# Sensor_Sound.net
KiCad netlist of a schematic drawn in EAGLE
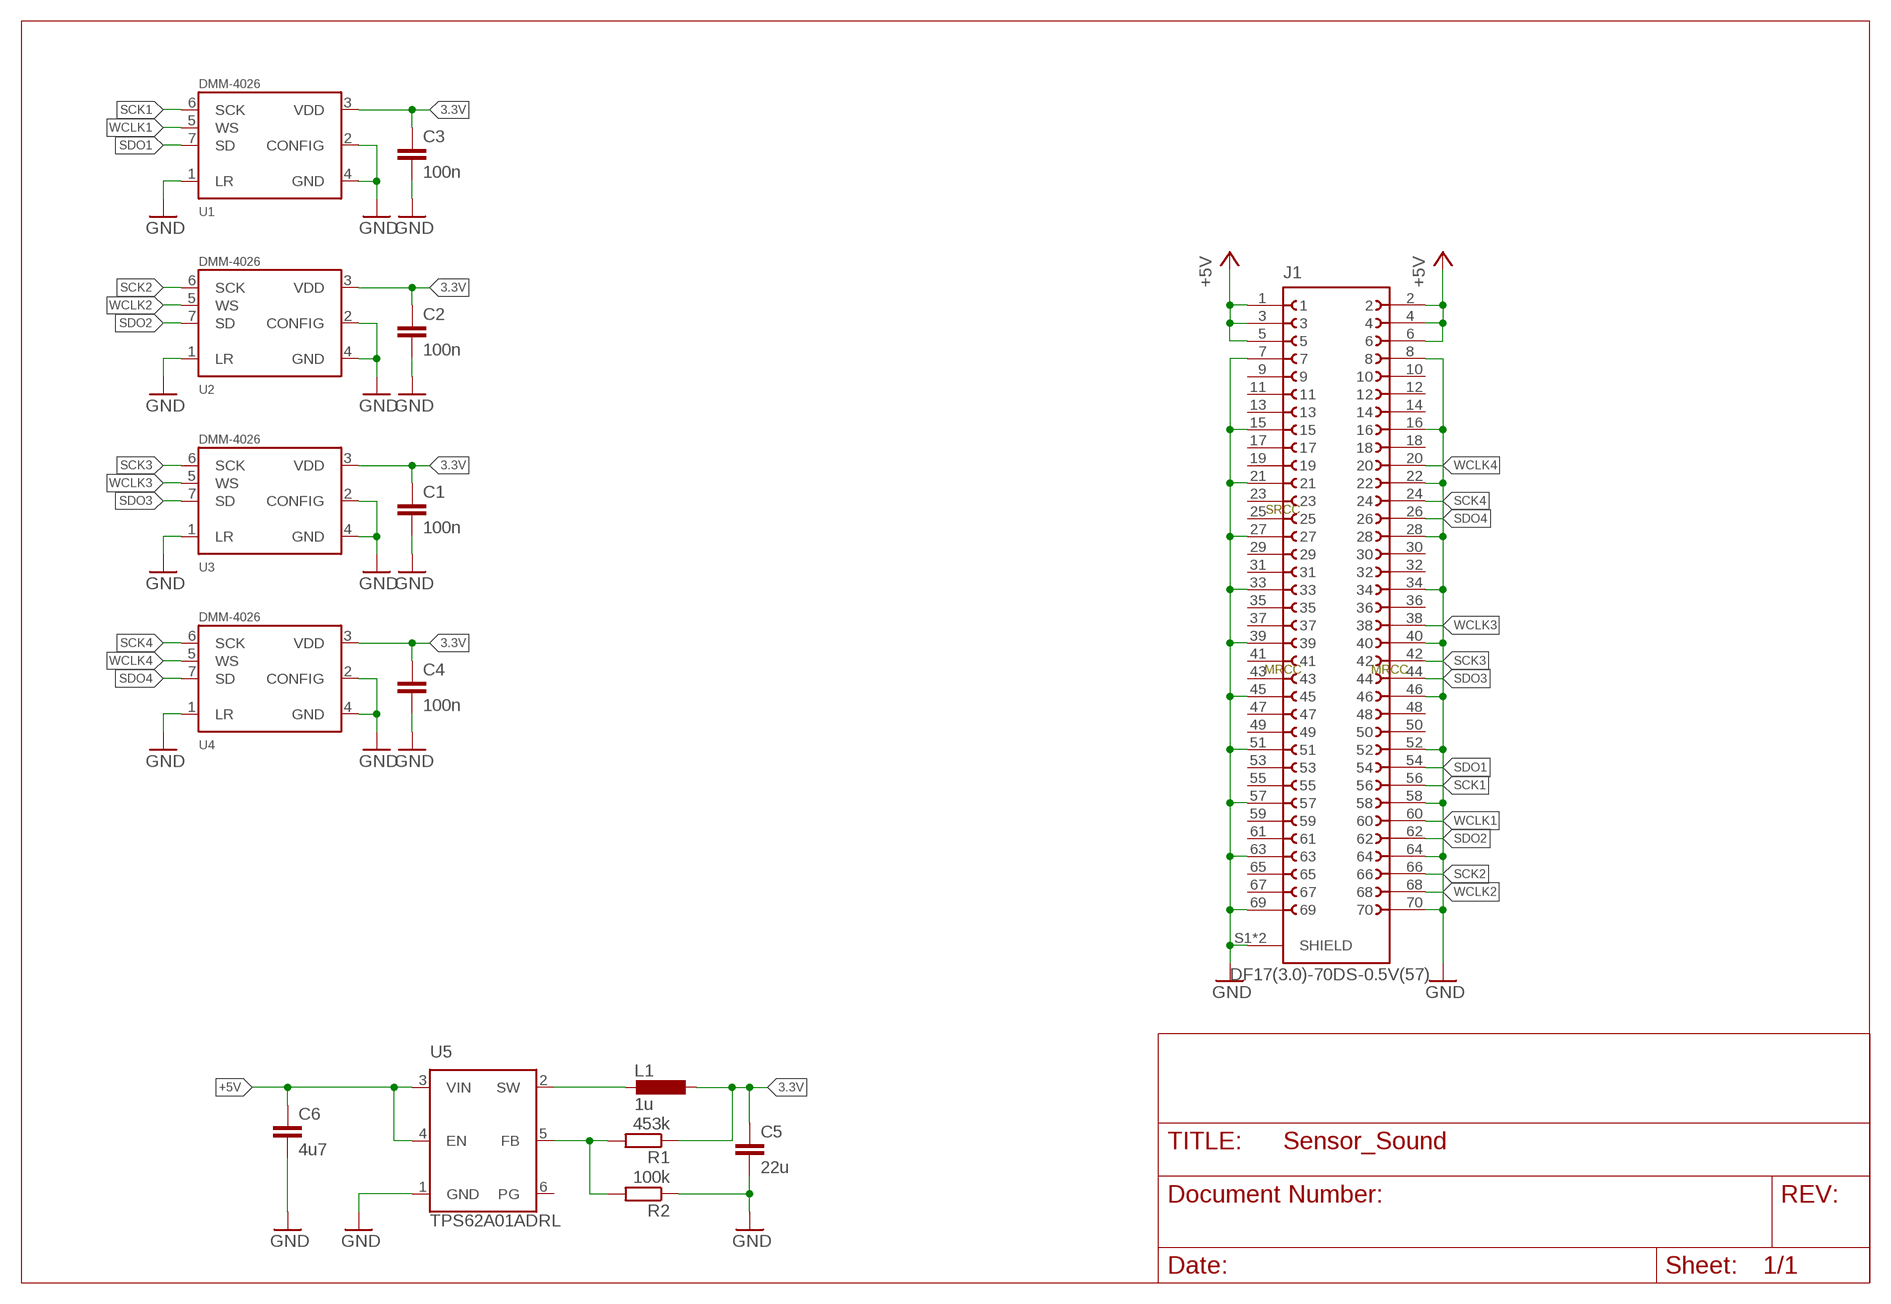
[diagram p0: schematic, sheet 1]

(export (version "E")
  (design (tool "Eeschema 10.0.6"))
  (components
    (comp (ref "C1")
      (value "100n")
      (footprint "eagle-import:C0402")
      (libsource (lib "eagle-import") (part "C-EUC0402"))
    )
    (comp (ref "C2")
      (value "100n")
      (footprint "eagle-import:C0402")
      (libsource (lib "eagle-import") (part "C-EUC0402"))
    )
    (comp (ref "C3")
      (value "100n")
      (footprint "eagle-import:C0402")
      (libsource (lib "eagle-import") (part "C-EUC0402"))
    )
    (comp (ref "C4")
      (value "100n")
      (footprint "eagle-import:C0402")
      (libsource (lib "eagle-import") (part "C-EUC0402"))
    )
    (comp (ref "C5")
      (value "22u")
      (footprint "eagle-import:C0603")
      (libsource (lib "eagle-import") (part "C-EUC0603"))
    )
    (comp (ref "C6")
      (value "4u7")
      (footprint "eagle-import:C0603")
      (libsource (lib "eagle-import") (part "C-EUC0603"))
    )
    (comp (ref "J1")
      (value "DF17(3.0)-70DS-0.5V(57)")
      (footprint "eagle-import:DF17(3.0)-70DS-0.5V(57)")
      (libsource (lib "eagle-import") (part "DF17(3.0)-70DS-0.5V(57)"))
    )
    (comp (ref "L1")
      (value "1u")
      (footprint "eagle-import:L1008")
      (fields (field (name "MPN") "LQM2HPN1R0MG0L"))
      (libsource (lib "eagle-import") (part "L-EU1008"))
    )
    (comp (ref "R1")
      (value "453k")
      (footprint "eagle-import:R0402")
      (libsource (lib "eagle-import") (part "R-EU_R0402"))
    )
    (comp (ref "R2")
      (value "100k")
      (footprint "eagle-import:R0402")
      (libsource (lib "eagle-import") (part "R-EU_R0402"))
    )
    (comp (ref "U1")
      (value "DMM-4026")
      (footprint "eagle-import:DMM-4026")
      (libsource (lib "eagle-import") (part "DMM-4026"))
    )
    (comp (ref "U2")
      (value "DMM-4026")
      (footprint "eagle-import:DMM-4026")
      (libsource (lib "eagle-import") (part "DMM-4026"))
    )
    (comp (ref "U3")
      (value "DMM-4026")
      (footprint "eagle-import:DMM-4026")
      (libsource (lib "eagle-import") (part "DMM-4026"))
    )
    (comp (ref "U4")
      (value "DMM-4026")
      (footprint "eagle-import:DMM-4026")
      (libsource (lib "eagle-import") (part "DMM-4026"))
    )
    (comp (ref "U5")
      (value "TPS62A01ADRL")
      (footprint "eagle-import:SOTFL50P160X60-6N")
      (fields (field (name "MANUFACTURER_PART_NUMBER") "TPS62A01ADRLR"))
      (libsource (lib "eagle-import") (part "TPS62A01ADRL"))
    )
  )
  (nets
    (net (code "1") (name "+5V") (class "Default")
      (node (ref "C6") (pin "1") (pinfunction "1_1") (pintype "passive"))
      (node (ref "J1") (pin "1") (pinfunction "1_1") (pintype "passive"))
      (node (ref "J1") (pin "2") (pinfunction "2_2") (pintype "passive"))
      (node (ref "J1") (pin "3") (pinfunction "3_3") (pintype "passive"))
      (node (ref "J1") (pin "4") (pinfunction "4_4") (pintype "passive"))
      (node (ref "J1") (pin "5") (pinfunction "5_5") (pintype "passive"))
      (node (ref "J1") (pin "6") (pinfunction "6_6") (pintype "passive"))
      (node (ref "U5") (pin "3") (pinfunction "VIN_3") (pintype "bidirectional"))
      (node (ref "U5") (pin "4") (pinfunction "EN_4") (pintype "bidirectional"))
    )
    (net (code "2") (name "3.3V") (class "Default")
      (node (ref "C1") (pin "1") (pinfunction "1_1") (pintype "passive"))
      (node (ref "C2") (pin "1") (pinfunction "1_1") (pintype "passive"))
      (node (ref "C3") (pin "1") (pinfunction "1_1") (pintype "passive"))
      (node (ref "C4") (pin "1") (pinfunction "1_1") (pintype "passive"))
      (node (ref "C5") (pin "1") (pinfunction "1_1") (pintype "passive"))
      (node (ref "L1") (pin "1") (pinfunction "1_1") (pintype "passive"))
      (node (ref "R1") (pin "1") (pinfunction "1_1") (pintype "passive"))
      (node (ref "U1") (pin "3") (pinfunction "VDD_3") (pintype "power_in"))
      (node (ref "U2") (pin "3") (pinfunction "VDD_3") (pintype "power_in"))
      (node (ref "U3") (pin "3") (pinfunction "VDD_3") (pintype "power_in"))
      (node (ref "U4") (pin "3") (pinfunction "VDD_3") (pintype "power_in"))
    )
    (net (code "3") (name "GND") (class "Default")
      (node (ref "C1") (pin "2") (pinfunction "2_2") (pintype "passive"))
      (node (ref "C2") (pin "2") (pinfunction "2_2") (pintype "passive"))
      (node (ref "C3") (pin "2") (pinfunction "2_2") (pintype "passive"))
      (node (ref "C4") (pin "2") (pinfunction "2_2") (pintype "passive"))
      (node (ref "C5") (pin "2") (pinfunction "2_2") (pintype "passive"))
      (node (ref "C6") (pin "2") (pinfunction "2_2") (pintype "passive"))
      (node (ref "J1") (pin "15") (pinfunction "15_15") (pintype "passive"))
      (node (ref "J1") (pin "16") (pinfunction "16_16") (pintype "passive"))
      (node (ref "J1") (pin "21") (pinfunction "21_21") (pintype "passive"))
      (node (ref "J1") (pin "22") (pinfunction "22_22") (pintype "passive"))
      (node (ref "J1") (pin "27") (pinfunction "27_27") (pintype "passive"))
      (node (ref "J1") (pin "28") (pinfunction "28_28") (pintype "passive"))
      (node (ref "J1") (pin "33") (pinfunction "33_33") (pintype "passive"))
      (node (ref "J1") (pin "34") (pinfunction "34_34") (pintype "passive"))
      (node (ref "J1") (pin "39") (pinfunction "39_39") (pintype "passive"))
      (node (ref "J1") (pin "40") (pinfunction "40_40") (pintype "passive"))
      (node (ref "J1") (pin "45") (pinfunction "45_45") (pintype "passive"))
      (node (ref "J1") (pin "46") (pinfunction "46_46") (pintype "passive"))
      (node (ref "J1") (pin "51") (pinfunction "51_51") (pintype "passive"))
      (node (ref "J1") (pin "52") (pinfunction "52_52") (pintype "passive"))
      (node (ref "J1") (pin "57") (pinfunction "57_57") (pintype "passive"))
      (node (ref "J1") (pin "58") (pinfunction "58_58") (pintype "passive"))
      (node (ref "J1") (pin "63") (pinfunction "63_63") (pintype "passive"))
      (node (ref "J1") (pin "64") (pinfunction "64_64") (pintype "passive"))
      (node (ref "J1") (pin "69") (pinfunction "69_69") (pintype "passive"))
      (node (ref "J1") (pin "7") (pinfunction "7_7") (pintype "passive"))
      (node (ref "J1") (pin "70") (pinfunction "70_70") (pintype "passive"))
      (node (ref "J1") (pin "8") (pinfunction "8_8") (pintype "passive"))
      (node (ref "J1") (pin "S1") (pinfunction "SHIELD_S1") (pintype "passive"))
      (node (ref "J1") (pin "S2") (pinfunction "SHIELD_S2") (pintype "passive"))
      (node (ref "R2") (pin "1") (pinfunction "1_1") (pintype "passive"))
      (node (ref "U1") (pin "1") (pinfunction "LR_1") (pintype "input"))
      (node (ref "U1") (pin "2") (pinfunction "CONFIG_2") (pintype "input"))
      (node (ref "U1") (pin "4") (pinfunction "GND_4") (pintype "power_in"))
      (node (ref "U2") (pin "1") (pinfunction "LR_1") (pintype "input"))
      (node (ref "U2") (pin "2") (pinfunction "CONFIG_2") (pintype "input"))
      (node (ref "U2") (pin "4") (pinfunction "GND_4") (pintype "power_in"))
      (node (ref "U3") (pin "1") (pinfunction "LR_1") (pintype "input"))
      (node (ref "U3") (pin "2") (pinfunction "CONFIG_2") (pintype "input"))
      (node (ref "U3") (pin "4") (pinfunction "GND_4") (pintype "power_in"))
      (node (ref "U4") (pin "1") (pinfunction "LR_1") (pintype "input"))
      (node (ref "U4") (pin "2") (pinfunction "CONFIG_2") (pintype "input"))
      (node (ref "U4") (pin "4") (pinfunction "GND_4") (pintype "power_in"))
      (node (ref "U5") (pin "1") (pinfunction "GND_1") (pintype "bidirectional"))
    )
    (net (code "4") (name "Net-(U5-FB)") (class "Default")
      (node (ref "R1") (pin "2") (pinfunction "2_2") (pintype "passive"))
      (node (ref "R2") (pin "2") (pinfunction "2_2") (pintype "passive"))
      (node (ref "U5") (pin "5") (pinfunction "FB_5") (pintype "bidirectional"))
    )
    (net (code "5") (name "Net-(U5-SW)") (class "Default")
      (node (ref "L1") (pin "2") (pinfunction "2_2") (pintype "passive"))
      (node (ref "U5") (pin "2") (pinfunction "SW_2") (pintype "bidirectional"))
    )
    (net (code "6") (name "SCK1") (class "Default")
      (node (ref "J1") (pin "56") (pinfunction "56_56") (pintype "passive"))
      (node (ref "U1") (pin "6") (pinfunction "SCK_6") (pintype "input"))
    )
    (net (code "7") (name "SCK2") (class "Default")
      (node (ref "J1") (pin "66") (pinfunction "66_66") (pintype "passive"))
      (node (ref "U2") (pin "6") (pinfunction "SCK_6") (pintype "input"))
    )
    (net (code "8") (name "SCK3") (class "Default")
      (node (ref "J1") (pin "42") (pinfunction "42_42") (pintype "passive"))
      (node (ref "U3") (pin "6") (pinfunction "SCK_6") (pintype "input"))
    )
    (net (code "9") (name "SCK4") (class "Default")
      (node (ref "J1") (pin "24") (pinfunction "24_24") (pintype "passive"))
      (node (ref "U4") (pin "6") (pinfunction "SCK_6") (pintype "input"))
    )
    (net (code "10") (name "SDO1") (class "Default")
      (node (ref "J1") (pin "54") (pinfunction "54_54") (pintype "passive"))
      (node (ref "U1") (pin "7") (pinfunction "SD_7") (pintype "output"))
    )
    (net (code "11") (name "SDO2") (class "Default")
      (node (ref "J1") (pin "62") (pinfunction "62_62") (pintype "passive"))
      (node (ref "U2") (pin "7") (pinfunction "SD_7") (pintype "output"))
    )
    (net (code "12") (name "SDO3") (class "Default")
      (node (ref "J1") (pin "44") (pinfunction "44_44") (pintype "passive"))
      (node (ref "U3") (pin "7") (pinfunction "SD_7") (pintype "output"))
    )
    (net (code "13") (name "SDO4") (class "Default")
      (node (ref "J1") (pin "26") (pinfunction "26_26") (pintype "passive"))
      (node (ref "U4") (pin "7") (pinfunction "SD_7") (pintype "output"))
    )
    (net (code "14") (name "WCLK1") (class "Default")
      (node (ref "J1") (pin "60") (pinfunction "60_60") (pintype "passive"))
      (node (ref "U1") (pin "5") (pinfunction "WS_5") (pintype "input"))
    )
    (net (code "15") (name "WCLK2") (class "Default")
      (node (ref "J1") (pin "68") (pinfunction "68_68") (pintype "passive"))
      (node (ref "U2") (pin "5") (pinfunction "WS_5") (pintype "input"))
    )
    (net (code "16") (name "WCLK3") (class "Default")
      (node (ref "J1") (pin "38") (pinfunction "38_38") (pintype "passive"))
      (node (ref "U3") (pin "5") (pinfunction "WS_5") (pintype "input"))
    )
    (net (code "17") (name "WCLK4") (class "Default")
      (node (ref "J1") (pin "20") (pinfunction "20_20") (pintype "passive"))
      (node (ref "U4") (pin "5") (pinfunction "WS_5") (pintype "input"))
    )
    (net (code "18") (name "unconnected-(J1-Pad9)") (class "Default")
      (node (ref "J1") (pin "9") (pinfunction "9_9") (pintype "passive"))
    )
    (net (code "19") (name "unconnected-(J1-Pad10)") (class "Default")
      (node (ref "J1") (pin "10") (pinfunction "10_10") (pintype "passive"))
    )
    (net (code "20") (name "unconnected-(J1-Pad11)") (class "Default")
      (node (ref "J1") (pin "11") (pinfunction "11_11") (pintype "passive"))
    )
    (net (code "21") (name "unconnected-(J1-Pad12)") (class "Default")
      (node (ref "J1") (pin "12") (pinfunction "12_12") (pintype "passive"))
    )
    (net (code "22") (name "unconnected-(J1-Pad13)") (class "Default")
      (node (ref "J1") (pin "13") (pinfunction "13_13") (pintype "passive"))
    )
    (net (code "23") (name "unconnected-(J1-Pad14)") (class "Default")
      (node (ref "J1") (pin "14") (pinfunction "14_14") (pintype "passive"))
    )
    (net (code "24") (name "unconnected-(J1-Pad17)") (class "Default")
      (node (ref "J1") (pin "17") (pinfunction "17_17") (pintype "passive"))
    )
    (net (code "25") (name "unconnected-(J1-Pad18)") (class "Default")
      (node (ref "J1") (pin "18") (pinfunction "18_18") (pintype "passive"))
    )
    (net (code "26") (name "unconnected-(J1-Pad19)") (class "Default")
      (node (ref "J1") (pin "19") (pinfunction "19_19") (pintype "passive"))
    )
    (net (code "27") (name "unconnected-(J1-Pad23)") (class "Default")
      (node (ref "J1") (pin "23") (pinfunction "23_23") (pintype "passive"))
    )
    (net (code "28") (name "unconnected-(J1-Pad25)") (class "Default")
      (node (ref "J1") (pin "25") (pinfunction "25_25") (pintype "passive"))
    )
    (net (code "29") (name "unconnected-(J1-Pad29)") (class "Default")
      (node (ref "J1") (pin "29") (pinfunction "29_29") (pintype "passive"))
    )
    (net (code "30") (name "unconnected-(J1-Pad30)") (class "Default")
      (node (ref "J1") (pin "30") (pinfunction "30_30") (pintype "passive"))
    )
    (net (code "31") (name "unconnected-(J1-Pad31)") (class "Default")
      (node (ref "J1") (pin "31") (pinfunction "31_31") (pintype "passive"))
    )
    (net (code "32") (name "unconnected-(J1-Pad32)") (class "Default")
      (node (ref "J1") (pin "32") (pinfunction "32_32") (pintype "passive"))
    )
    (net (code "33") (name "unconnected-(J1-Pad35)") (class "Default")
      (node (ref "J1") (pin "35") (pinfunction "35_35") (pintype "passive"))
    )
    (net (code "34") (name "unconnected-(J1-Pad36)") (class "Default")
      (node (ref "J1") (pin "36") (pinfunction "36_36") (pintype "passive"))
    )
    (net (code "35") (name "unconnected-(J1-Pad37)") (class "Default")
      (node (ref "J1") (pin "37") (pinfunction "37_37") (pintype "passive"))
    )
    (net (code "36") (name "unconnected-(J1-Pad41)") (class "Default")
      (node (ref "J1") (pin "41") (pinfunction "41_41") (pintype "passive"))
    )
    (net (code "37") (name "unconnected-(J1-Pad43)") (class "Default")
      (node (ref "J1") (pin "43") (pinfunction "43_43") (pintype "passive"))
    )
    (net (code "38") (name "unconnected-(J1-Pad47)") (class "Default")
      (node (ref "J1") (pin "47") (pinfunction "47_47") (pintype "passive"))
    )
    (net (code "39") (name "unconnected-(J1-Pad48)") (class "Default")
      (node (ref "J1") (pin "48") (pinfunction "48_48") (pintype "passive"))
    )
    (net (code "40") (name "unconnected-(J1-Pad49)") (class "Default")
      (node (ref "J1") (pin "49") (pinfunction "49_49") (pintype "passive"))
    )
    (net (code "41") (name "unconnected-(J1-Pad50)") (class "Default")
      (node (ref "J1") (pin "50") (pinfunction "50_50") (pintype "passive"))
    )
    (net (code "42") (name "unconnected-(J1-Pad53)") (class "Default")
      (node (ref "J1") (pin "53") (pinfunction "53_53") (pintype "passive"))
    )
    (net (code "43") (name "unconnected-(J1-Pad55)") (class "Default")
      (node (ref "J1") (pin "55") (pinfunction "55_55") (pintype "passive"))
    )
    (net (code "44") (name "unconnected-(J1-Pad59)") (class "Default")
      (node (ref "J1") (pin "59") (pinfunction "59_59") (pintype "passive"))
    )
    (net (code "45") (name "unconnected-(J1-Pad61)") (class "Default")
      (node (ref "J1") (pin "61") (pinfunction "61_61") (pintype "passive"))
    )
    (net (code "46") (name "unconnected-(J1-Pad65)") (class "Default")
      (node (ref "J1") (pin "65") (pinfunction "65_65") (pintype "passive"))
    )
    (net (code "47") (name "unconnected-(J1-Pad67)") (class "Default")
      (node (ref "J1") (pin "67") (pinfunction "67_67") (pintype "passive"))
    )
    (net (code "48") (name "unconnected-(U5-PG-Pad6)") (class "Default")
      (node (ref "U5") (pin "6") (pinfunction "PG_6") (pintype "bidirectional"))
    )
  )
)
